# Regulation_Charging.net
KiCad netlist of a schematic drawn in Altium Designer
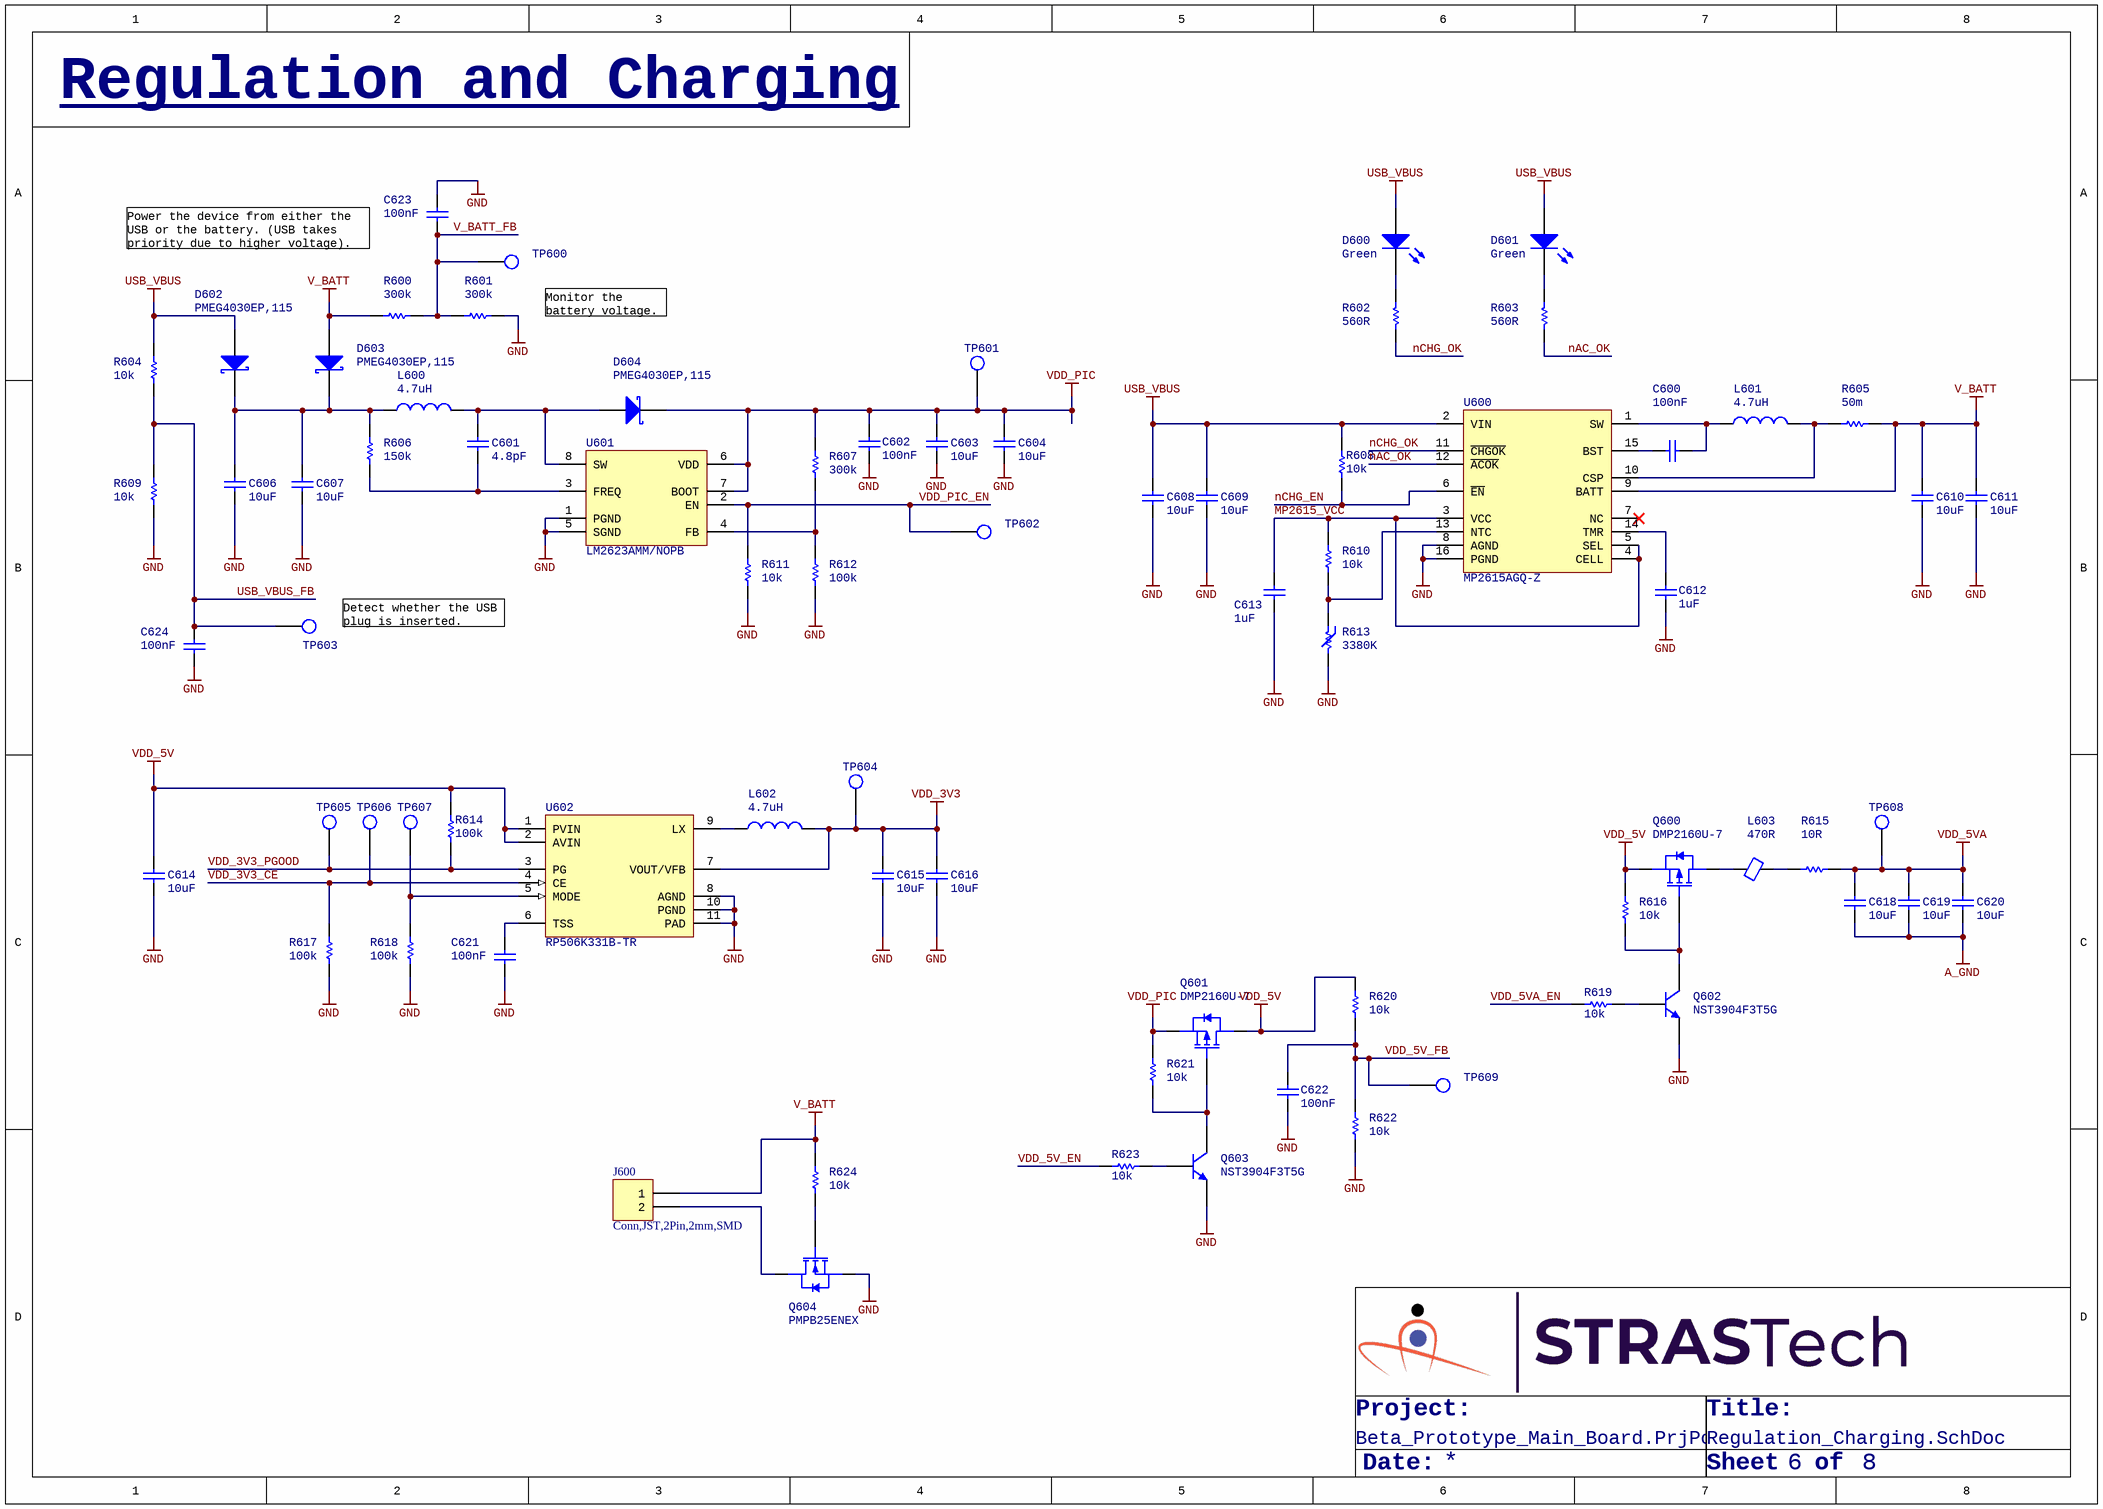
[diagram p0: Regulation_Charging.SchDoc]

(export (version "E")
  (design (tool "Eeschema 10.0.6"))
  (components
    (comp (ref "C600")
      (value "100nF")
      (footprint "Cap,SMD,0402")
      (description "0.1µF ±10% 25V Ceramic Capacitor X7R 0402 (1005 Metric)")
      (fields
        (field (name "VENDOR PART NUMBER") "490-14603-1-ND")
        (field (name "MANUFACTURER") "Murata Electronics")
        (field (name "CREATEDBY") "Judd Foster")
      )
      (libsource (lib "symbols") (part "CAP,Cer,100nF,25VDC,X7R,0402"))
    )
    (comp (ref "C601")
      (value "4.8pF")
      (footprint "Cap,SMD,0402")
      (description "4.8 pF ±0.25pF 50V Ceramic Capacitor C0G, NP0 0402 (1005 Metric)")
      (fields
        (field (name "VENDOR PART NUMBER") "490-17481-1-ND")
        (field (name "MANUFACTURER") "Murata Electronics")
        (field (name "CREATEDBY") "Judd Foster")
      )
      (libsource (lib "symbols") (part "CAP,Cer,4.8pF,50VDC,C0G/NP0,0402"))
    )
    (comp (ref "C602")
      (value "100nF")
      (footprint "Cap,SMD,0402")
      (description "0.1µF ±10% 25V Ceramic Capacitor X7R 0402 (1005 Metric)")
      (fields
        (field (name "VENDOR PART NUMBER") "490-14603-1-ND")
        (field (name "MANUFACTURER") "Murata Electronics")
        (field (name "CREATEDBY") "Judd Foster")
      )
      (libsource (lib "symbols") (part "CAP,Cer,100nF,25VDC,X7R,0402"))
    )
    (comp (ref "C603")
      (value "10uF")
      (footprint "Cap,SMD,0402")
      (description "10 µF ±20% 10V Ceramic Capacitor X5R 0402 (1005 Metric)")
      (fields
        (field (name "VENDOR PART NUMBER") "1276-1450-1-ND")
        (field (name "MANUFACTURER") "Samsung Electro-Mechanics")
        (field (name "CREATEDBY") "Judd Foster")
      )
      (libsource (lib "symbols") (part "CAP,Cer,10uF,10VDC,X5R,0402"))
    )
    (comp (ref "C604")
      (value "10uF")
      (footprint "Cap,SMD,0402")
      (description "10 µF ±20% 10V Ceramic Capacitor X5R 0402 (1005 Metric)")
      (fields
        (field (name "VENDOR PART NUMBER") "1276-1450-1-ND")
        (field (name "MANUFACTURER") "Samsung Electro-Mechanics")
        (field (name "CREATEDBY") "Judd Foster")
      )
      (libsource (lib "symbols") (part "CAP,Cer,10uF,10VDC,X5R,0402"))
    )
    (comp (ref "C606")
      (value "10uF")
      (footprint "Cap,SMD,0402")
      (description "10 µF ±20% 10V Ceramic Capacitor X5R 0402 (1005 Metric)")
      (fields
        (field (name "VENDOR PART NUMBER") "1276-1450-1-ND")
        (field (name "MANUFACTURER") "Samsung Electro-Mechanics")
        (field (name "CREATEDBY") "Judd Foster")
      )
      (libsource (lib "symbols") (part "CAP,Cer,10uF,10VDC,X5R,0402"))
    )
    (comp (ref "C607")
      (value "10uF")
      (footprint "Cap,SMD,0402")
      (description "10 µF ±20% 10V Ceramic Capacitor X5R 0402 (1005 Metric)")
      (fields
        (field (name "VENDOR PART NUMBER") "1276-1450-1-ND")
        (field (name "MANUFACTURER") "Samsung Electro-Mechanics")
        (field (name "CREATEDBY") "Judd Foster")
      )
      (libsource (lib "symbols") (part "CAP,Cer,10uF,10VDC,X5R,0402"))
    )
    (comp (ref "C608")
      (value "10uF")
      (footprint "Cap,SMD,0402")
      (description "10 µF ±20% 10V Ceramic Capacitor X5R 0402 (1005 Metric)")
      (fields
        (field (name "VENDOR PART NUMBER") "1276-1450-1-ND")
        (field (name "MANUFACTURER") "Samsung Electro-Mechanics")
        (field (name "CREATEDBY") "Judd Foster")
      )
      (libsource (lib "symbols") (part "CAP,Cer,10uF,10VDC,X5R,0402"))
    )
    (comp (ref "C609")
      (value "10uF")
      (footprint "Cap,SMD,0402")
      (description "10 µF ±20% 10V Ceramic Capacitor X5R 0402 (1005 Metric)")
      (fields
        (field (name "VENDOR PART NUMBER") "1276-1450-1-ND")
        (field (name "MANUFACTURER") "Samsung Electro-Mechanics")
        (field (name "CREATEDBY") "Judd Foster")
      )
      (libsource (lib "symbols") (part "CAP,Cer,10uF,10VDC,X5R,0402"))
    )
    (comp (ref "C610")
      (value "10uF")
      (footprint "Cap,SMD,0402")
      (description "10 µF ±20% 10V Ceramic Capacitor X5R 0402 (1005 Metric)")
      (fields
        (field (name "VENDOR PART NUMBER") "1276-1450-1-ND")
        (field (name "MANUFACTURER") "Samsung Electro-Mechanics")
        (field (name "CREATEDBY") "Judd Foster")
      )
      (libsource (lib "symbols") (part "CAP,Cer,10uF,10VDC,X5R,0402"))
    )
    (comp (ref "C611")
      (value "10uF")
      (footprint "Cap,SMD,0402")
      (description "10 µF ±20% 10V Ceramic Capacitor X5R 0402 (1005 Metric)")
      (fields
        (field (name "VENDOR PART NUMBER") "1276-1450-1-ND")
        (field (name "MANUFACTURER") "Samsung Electro-Mechanics")
        (field (name "CREATEDBY") "Judd Foster")
      )
      (libsource (lib "symbols") (part "CAP,Cer,10uF,10VDC,X5R,0402"))
    )
    (comp (ref "C612")
      (value "1uF")
      (footprint "Cap,SMD,0402")
      (description "1 µF ±10% 35V Ceramic Capacitor X5R 0402 (1005 Metric)")
      (fields
        (field (name "VENDOR PART NUMBER") "445-9073-1-ND")
        (field (name "MANUFACTURER") "TDK Corporation")
        (field (name "CREATEDBY") "Judd Foster")
      )
      (libsource (lib "symbols") (part "CAP,Cer,1uF,35VDC,X5R,0402"))
    )
    (comp (ref "C613")
      (value "1uF")
      (footprint "Cap,SMD,0402")
      (description "1 µF ±10% 35V Ceramic Capacitor X5R 0402 (1005 Metric)")
      (fields
        (field (name "VENDOR PART NUMBER") "445-9073-1-ND")
        (field (name "MANUFACTURER") "TDK Corporation")
        (field (name "CREATEDBY") "Judd Foster")
      )
      (libsource (lib "symbols") (part "CAP,Cer,1uF,35VDC,X5R,0402"))
    )
    (comp (ref "C614")
      (value "10uF")
      (footprint "Cap,SMD,0402")
      (description "10 µF ±20% 10V Ceramic Capacitor X5R 0402 (1005 Metric)")
      (fields
        (field (name "VENDOR PART NUMBER") "1276-1450-1-ND")
        (field (name "MANUFACTURER") "Samsung Electro-Mechanics")
        (field (name "CREATEDBY") "Judd Foster")
      )
      (libsource (lib "symbols") (part "CAP,Cer,10uF,10VDC,X5R,0402"))
    )
    (comp (ref "C615")
      (value "10uF")
      (footprint "Cap,SMD,0402")
      (description "10 µF ±20% 10V Ceramic Capacitor X5R 0402 (1005 Metric)")
      (fields
        (field (name "VENDOR PART NUMBER") "1276-1450-1-ND")
        (field (name "MANUFACTURER") "Samsung Electro-Mechanics")
        (field (name "CREATEDBY") "Judd Foster")
      )
      (libsource (lib "symbols") (part "CAP,Cer,10uF,10VDC,X5R,0402"))
    )
    (comp (ref "C616")
      (value "10uF")
      (footprint "Cap,SMD,0402")
      (description "10 µF ±20% 10V Ceramic Capacitor X5R 0402 (1005 Metric)")
      (fields
        (field (name "VENDOR PART NUMBER") "1276-1450-1-ND")
        (field (name "MANUFACTURER") "Samsung Electro-Mechanics")
        (field (name "CREATEDBY") "Judd Foster")
      )
      (libsource (lib "symbols") (part "CAP,Cer,10uF,10VDC,X5R,0402"))
    )
    (comp (ref "C618")
      (value "10uF")
      (footprint "Cap,SMD,0402")
      (description "10 µF ±20% 10V Ceramic Capacitor X5R 0402 (1005 Metric)")
      (fields
        (field (name "VENDOR PART NUMBER") "1276-1450-1-ND")
        (field (name "MANUFACTURER") "Samsung Electro-Mechanics")
        (field (name "CREATEDBY") "Judd Foster")
      )
      (libsource (lib "symbols") (part "CAP,Cer,10uF,10VDC,X5R,0402"))
    )
    (comp (ref "C619")
      (value "10uF")
      (footprint "Cap,SMD,0402")
      (description "10 µF ±20% 10V Ceramic Capacitor X5R 0402 (1005 Metric)")
      (fields
        (field (name "VENDOR PART NUMBER") "1276-1450-1-ND")
        (field (name "MANUFACTURER") "Samsung Electro-Mechanics")
        (field (name "CREATEDBY") "Judd Foster")
      )
      (libsource (lib "symbols") (part "CAP,Cer,10uF,10VDC,X5R,0402"))
    )
    (comp (ref "C620")
      (value "10uF")
      (footprint "Cap,SMD,0402")
      (description "10 µF ±20% 10V Ceramic Capacitor X5R 0402 (1005 Metric)")
      (fields
        (field (name "VENDOR PART NUMBER") "1276-1450-1-ND")
        (field (name "MANUFACTURER") "Samsung Electro-Mechanics")
        (field (name "CREATEDBY") "Judd Foster")
      )
      (libsource (lib "symbols") (part "CAP,Cer,10uF,10VDC,X5R,0402"))
    )
    (comp (ref "C621")
      (value "100nF")
      (footprint "Cap,SMD,0402")
      (description "0.1µF ±10% 25V Ceramic Capacitor X7R 0402 (1005 Metric)")
      (fields
        (field (name "VENDOR PART NUMBER") "490-14603-1-ND")
        (field (name "MANUFACTURER") "Murata Electronics")
        (field (name "CREATEDBY") "Judd Foster")
      )
      (libsource (lib "symbols") (part "CAP,Cer,100nF,25VDC,X7R,0402"))
    )
    (comp (ref "C622")
      (value "100nF")
      (footprint "Cap,SMD,0402")
      (description "0.1µF ±10% 25V Ceramic Capacitor X7R 0402 (1005 Metric)")
      (fields
        (field (name "VENDOR PART NUMBER") "490-14603-1-ND")
        (field (name "MANUFACTURER") "Murata Electronics")
        (field (name "CREATEDBY") "Judd Foster")
      )
      (libsource (lib "symbols") (part "CAP,Cer,100nF,25VDC,X7R,0402"))
    )
    (comp (ref "C623")
      (value "100nF")
      (footprint "Cap,SMD,0402")
      (description "0.1µF ±10% 25V Ceramic Capacitor X7R 0402 (1005 Metric)")
      (fields
        (field (name "VENDOR PART NUMBER") "490-14603-1-ND")
        (field (name "MANUFACTURER") "Murata Electronics")
        (field (name "CREATEDBY") "Judd Foster")
      )
      (libsource (lib "symbols") (part "CAP,Cer,100nF,25VDC,X7R,0402"))
    )
    (comp (ref "C624")
      (value "100nF")
      (footprint "Cap,SMD,0402")
      (description "0.1µF ±10% 25V Ceramic Capacitor X7R 0402 (1005 Metric)")
      (fields
        (field (name "VENDOR PART NUMBER") "490-14603-1-ND")
        (field (name "MANUFACTURER") "Murata Electronics")
        (field (name "CREATEDBY") "Judd Foster")
      )
      (libsource (lib "symbols") (part "CAP,Cer,100nF,25VDC,X7R,0402"))
    )
    (comp (ref "D600")
      (value "Green")
      (footprint "LED,0603")
      (description "Green 530nm LED Indication - Discrete 3V 0603 (1608 Metric)")
      (fields
        (field (name "MANUFACTURER") "Stanley Electric Co")
        (field (name "MANUFACTURER PART NUMBER") "THG1111C-0005-TR")
        (field (name "CREATEDBY") "Judd Foster")
      )
      (libsource (lib "symbols") (part "LED,Green,SMD,0603"))
    )
    (comp (ref "D601")
      (value "Green")
      (footprint "LED,0603")
      (description "Green 530nm LED Indication - Discrete 3V 0603 (1608 Metric)")
      (fields
        (field (name "MANUFACTURER") "Stanley Electric Co")
        (field (name "MANUFACTURER PART NUMBER") "THG1111C-0005-TR")
        (field (name "CREATEDBY") "Judd Foster")
      )
      (libsource (lib "symbols") (part "LED,Green,SMD,0603"))
    )
    (comp (ref "D602")
      (value "PMEG4030EP,115")
      (footprint "SOD128")
      (description "Diode Schottky 40V 3A Surface Mount CFP5")
      (fields
        (field (name "MANUFACTURER") "Nexperia USA Inc.")
        (field (name "VENDOR PART NUMBER") "1727-5841-1-ND")
        (field (name "CREATEDBY") "Judd Foster")
      )
      (libsource (lib "symbols") (part "DIODE,Schottky,40V,3A,SMD"))
    )
    (comp (ref "D603")
      (value "PMEG4030EP,115")
      (footprint "SOD128")
      (description "Diode Schottky 40V 3A Surface Mount CFP5")
      (fields
        (field (name "MANUFACTURER") "Nexperia USA Inc.")
        (field (name "VENDOR PART NUMBER") "1727-5841-1-ND")
        (field (name "CREATEDBY") "Judd Foster")
      )
      (libsource (lib "symbols") (part "DIODE,Schottky,40V,3A,SMD"))
    )
    (comp (ref "D604")
      (value "PMEG4030EP,115")
      (footprint "SOD128")
      (description "Diode Schottky 40V 3A Surface Mount CFP5")
      (fields
        (field (name "MANUFACTURER") "Nexperia USA Inc.")
        (field (name "VENDOR PART NUMBER") "1727-5841-1-ND")
        (field (name "CREATEDBY") "Judd Foster")
      )
      (libsource (lib "symbols") (part "DIODE,Schottky,40V,3A,SMD"))
    )
    (comp (ref "J600")
      (value "Conn,JST,2Pin,2mm,SMD")
      (footprint "Conn,JST,2Pin,2mm,SMD")
      (description "Connector Header Surface Mount, Right Angle 2 position 0.079\" (2.00mm)")
      (fields
        (field (name "VENDOR PART NUMBER") "H125443CT-ND")
        (field (name "MANUFACTURER") "Hirose Electric Co Ltd")
        (field (name "CREATED BY") "Judd Foster")
      )
      (libsource (lib "symbols") (part "Conn,JST,2Pin,2mm,SMD"))
    )
    (comp (ref "L600")
      (value "4.7uH")
      (footprint "IND,WIREWOUND,4.9x4.9,SMD")
      (description "4.7µH Shielded Wirewound Inductor 2.6A 45.5mOhm Max Nonstandard")
      (fields
        (field (name "VENDOR PART NUMBER") "587-3605-1-ND")
        (field (name "MANUFACTURER") "Taiyo Yuden")
        (field (name "CREATEDBY") "Judd Foster")
      )
      (libsource (lib "symbols") (part "IND,4.7uH,2.6A,Wirewound,SMD"))
    )
    (comp (ref "L601")
      (value "4.7uH")
      (footprint "IND,WIREWOUND,4.9x4.9,SMD")
      (description "4.7µH Shielded Wirewound Inductor 2.6A 45.5mOhm Max Nonstandard")
      (fields
        (field (name "VENDOR PART NUMBER") "587-3605-1-ND")
        (field (name "MANUFACTURER") "Taiyo Yuden")
        (field (name "CREATEDBY") "Judd Foster")
      )
      (libsource (lib "symbols") (part "IND,4.7uH,2.6A,Wirewound,SMD"))
    )
    (comp (ref "L602")
      (value "4.7uH")
      (footprint "IND,WIREWOUND,4.9x4.9,SMD")
      (description "4.7µH Shielded Wirewound Inductor 2.6A 45.5mOhm Max Nonstandard")
      (fields
        (field (name "VENDOR PART NUMBER") "587-3605-1-ND")
        (field (name "MANUFACTURER") "Taiyo Yuden")
        (field (name "CREATEDBY") "Judd Foster")
      )
      (libsource (lib "symbols") (part "IND,4.7uH,2.6A,Wirewound,SMD"))
    )
    (comp (ref "L603")
      (value "470R")
      (footprint "IND,0402")
      (description "470 Ohms @ 100 MHz 1 Power Line Ferrite Bead 0402 (1005 Metric) 1A 200mOhm")
      (fields
        (field (name "VENDOR PART NUMBER") "490-10662-1-ND")
        (field (name "MANUFACTURER") "Murata Electronics")
        (field (name "CREATEDBY") "Judd Foster")
      )
      (libsource (lib "symbols") (part "Ferrite,470R@100MHz,0402"))
    )
    (comp (ref "Q600")
      (value "DMP2160U-7")
      (footprint "SOT23-3")
      (description "P-Channel 20 V 3.2A (Ta) 1.4W (Ta) Surface Mount SOT-23-3")
      (fields
        (field (name "MANUFACTURER") "Diodes Incorporated")
        (field (name "VENDOR PART NUMBER") "DMP2160UDICT-ND")
        (field (name "CREATEDBY") "Judd Foster")
      )
      (libsource (lib "symbols") (part "MOSFET,P Ch,20V,3.2A"))
    )
    (comp (ref "Q601")
      (value "DMP2160U-7")
      (footprint "SOT23-3")
      (description "P-Channel 20 V 3.2A (Ta) 1.4W (Ta) Surface Mount SOT-23-3")
      (fields
        (field (name "MANUFACTURER") "Diodes Incorporated")
        (field (name "VENDOR PART NUMBER") "DMP2160UDICT-ND")
        (field (name "CREATEDBY") "Judd Foster")
      )
      (libsource (lib "symbols") (part "MOSFET,P Ch,20V,3.2A"))
    )
    (comp (ref "Q602")
      (value "NST3904F3T5G")
      (footprint "SOT1123")
      (description "Bipolar (BJT) Transistor NPN 40 V 200 mA 200MHz 290 mW Surface Mount SOT-1123")
      (fields
        (field (name "MANUFACTURER") "ON Semiconductor")
        (field (name "VENDOR PART NUMBER") "NST3904F3T5GOSCT-ND")
        (field (name "CREATEDBY") "Judd Foster")
      )
      (libsource (lib "symbols") (part "Trans,NPN,40V,200mA,SOT1123"))
    )
    (comp (ref "Q603")
      (value "NST3904F3T5G")
      (footprint "SOT1123")
      (description "Bipolar (BJT) Transistor NPN 40 V 200 mA 200MHz 290 mW Surface Mount SOT-1123")
      (fields
        (field (name "MANUFACTURER") "ON Semiconductor")
        (field (name "VENDOR PART NUMBER") "NST3904F3T5GOSCT-ND")
        (field (name "CREATEDBY") "Judd Foster")
      )
      (libsource (lib "symbols") (part "Trans,NPN,40V,200mA,SOT1123"))
    )
    (comp (ref "Q604")
      (value "PMPB25ENEX")
      (footprint "IC,WDFN-6,P0.65")
      (description "N-Channel 30 V 10A (Ta) 2.1W (Ta) Surface Mount DFN2020MD-6")
      (fields
        (field (name "MANUFACTURER") "Nexperia USA Inc.")
        (field (name "VENDOR PART NUMBER") "1727-7662-1-ND")
        (field (name "CREATEDBY") "Ritesh Nandakumar")
      )
      (libsource (lib "symbols") (part "MOSFET,N Ch,30V,10A"))
    )
    (comp (ref "R600")
      (value "300k")
      (footprint "RES,0402")
      (description "300 kOhms ±1% 0.063W, 1/16W Chip Resistor 0402 (1005 Metric) Automotive AEC-Q200 Thick Film")
      (fields
        (field (name "MANUFACTURER") "Stackpole Electronics Inc")
        (field (name "MANUFACTURER PART NUMBER") "RMCF0402FT300K")
        (field (name "CREATEDBY") "Judd Foster")
      )
      (libsource (lib "symbols") (part "RES,300k,1%,0.063W,0402"))
    )
    (comp (ref "R601")
      (value "300k")
      (footprint "RES,0402")
      (description "300 kOhms ±1% 0.063W, 1/16W Chip Resistor 0402 (1005 Metric) Automotive AEC-Q200 Thick Film")
      (fields
        (field (name "MANUFACTURER") "Stackpole Electronics Inc")
        (field (name "MANUFACTURER PART NUMBER") "RMCF0402FT300K")
        (field (name "CREATEDBY") "Judd Foster")
      )
      (libsource (lib "symbols") (part "RES,300k,1%,0.063W,0402"))
    )
    (comp (ref "R602")
      (value "560R")
      (footprint "RES,0402")
      (fields
        (field (name "MANUFACTURER") "TE Connectivity Passive Product")
        (field (name "MANUFACTURER PART NUMBER") "CRGCQ0402F560R")
        (field (name "VENDOR PART NUMBER") "A129624CT-ND")
        (field (name "CREATEDBY") "Judd Foster")
      )
      (libsource (lib "symbols") (part "RES,560R,1%,0.063W,0402"))
    )
    (comp (ref "R603")
      (value "560R")
      (footprint "RES,0402")
      (fields
        (field (name "MANUFACTURER") "TE Connectivity Passive Product")
        (field (name "MANUFACTURER PART NUMBER") "CRGCQ0402F560R")
        (field (name "VENDOR PART NUMBER") "A129624CT-ND")
        (field (name "CREATEDBY") "Judd Foster")
      )
      (libsource (lib "symbols") (part "RES,560R,1%,0.063W,0402"))
    )
    (comp (ref "R604")
      (value "10k")
      (footprint "RES,0402")
      (description "10 kOhms ±5% 0.063W, 1/16W Chip Resistor 0402 (1005 Metric) Automotive AEC-Q200 Thick Film")
      (fields
        (field (name "VENDOR PART NUMBER") "RMCF0402JT10K0CT-ND")
        (field (name "MANUFACTURER") "Stackpole Electronics Inc")
        (field (name "CREATEDBY") "Judd Foster")
      )
      (libsource (lib "symbols") (part "RES,10k,5%,0.063W,0402"))
    )
    (comp (ref "R605")
      (value "50m")
      (footprint "RES,1206")
      (description "50 mOhms ±1% 0.5W, 1/2W Chip Resistor 1206 (3216 Metric) Current Sense Metal Film")
      (fields
        (field (name "MANUFACTURER") "Ohmite")
        (field (name "MANUFACTURER PART NUMBER") "KDV12FR050ET")
        (field (name "CREATEDBY") "Judd Foster")
      )
      (libsource (lib "symbols") (part "RES,50m,1%,0.5W,1206"))
    )
    (comp (ref "R606")
      (value "150k")
      (footprint "RES,0402")
      (description "150 kOhms ±1% 0.063W, 1/16W Chip Resistor 0402 (1005 Metric) Automotive AEC-Q200 Thick Film")
      (fields
        (field (name "MANUFACTURER") "Stackpole Electronics Inc")
        (field (name "MANUFACTURER PART NUMBER") "RMCF0402FT150K")
        (field (name "CREATEDBY") "Judd Foster")
      )
      (libsource (lib "symbols") (part "RES,150k,1%,0.1W,0402"))
    )
    (comp (ref "R607")
      (value "300k")
      (footprint "RES,0402")
      (description "300 kOhms ±1% 0.063W, 1/16W Chip Resistor 0402 (1005 Metric) Automotive AEC-Q200 Thick Film")
      (fields
        (field (name "MANUFACTURER") "Stackpole Electronics Inc")
        (field (name "MANUFACTURER PART NUMBER") "RMCF0402FT300K")
        (field (name "CREATEDBY") "Judd Foster")
      )
      (libsource (lib "symbols") (part "RES,300k,1%,0.063W,0402"))
    )
    (comp (ref "R608")
      (value "10k")
      (footprint "RES,0402")
      (description "10 kOhms ±5% 0.063W, 1/16W Chip Resistor 0402 (1005 Metric) Automotive AEC-Q200 Thick Film")
      (fields
        (field (name "VENDOR PART NUMBER") "RMCF0402JT10K0CT-ND")
        (field (name "MANUFACTURER") "Stackpole Electronics Inc")
        (field (name "CREATEDBY") "Judd Foster")
      )
      (libsource (lib "symbols") (part "RES,10k,5%,0.063W,0402"))
    )
    (comp (ref "R609")
      (value "10k")
      (footprint "RES,0402")
      (description "10 kOhms ±5% 0.063W, 1/16W Chip Resistor 0402 (1005 Metric) Automotive AEC-Q200 Thick Film")
      (fields
        (field (name "VENDOR PART NUMBER") "RMCF0402JT10K0CT-ND")
        (field (name "MANUFACTURER") "Stackpole Electronics Inc")
        (field (name "CREATEDBY") "Judd Foster")
      )
      (libsource (lib "symbols") (part "RES,10k,5%,0.063W,0402"))
    )
    (comp (ref "R610")
      (value "10k")
      (footprint "RES,0402")
      (description "10 kOhms ±5% 0.063W, 1/16W Chip Resistor 0402 (1005 Metric) Automotive AEC-Q200 Thick Film")
      (fields
        (field (name "VENDOR PART NUMBER") "RMCF0402JT10K0CT-ND")
        (field (name "MANUFACTURER") "Stackpole Electronics Inc")
        (field (name "CREATEDBY") "Judd Foster")
      )
      (libsource (lib "symbols") (part "RES,10k,5%,0.063W,0402"))
    )
    (comp (ref "R611")
      (value "10k")
      (footprint "RES,0402")
      (description "10 kOhms ±5% 0.063W, 1/16W Chip Resistor 0402 (1005 Metric) Automotive AEC-Q200 Thick Film")
      (fields
        (field (name "VENDOR PART NUMBER") "RMCF0402JT10K0CT-ND")
        (field (name "MANUFACTURER") "Stackpole Electronics Inc")
        (field (name "CREATEDBY") "Judd Foster")
      )
      (libsource (lib "symbols") (part "RES,10k,5%,0.063W,0402"))
    )
    (comp (ref "R612")
      (value "100k")
      (footprint "RES,0402")
      (description "100 kOhms ±5% 0.1W, 1/10W Chip Resistor 0402 (1005 Metric) Automotive AEC-Q200 Thick Film")
      (fields
        (field (name "MANUFACTURER") "Panasonic Electronic Components")
        (field (name "MANUFACTURER PART NUMBER") "ERJ-2GEJ104X")
        (field (name "CREATEDBY") "Judd Foster")
      )
      (libsource (lib "symbols") (part "RES,100k,5%,0.1W,0402"))
    )
    (comp (ref "R613")
      (value "3380K")
      (footprint "RES,0402")
      (description "NTC Thermistor 10k 0402 (1005 Metric)")
      (fields
        (field (name "MANUFACTURER") "Murata Electronics")
        (field (name "MANUFACTURER PART NUMBER") "NCU15XH103J6SRC")
        (field (name "CREATEDBY") "Judd Foster")
      )
      (libsource (lib "symbols") (part "RES,Thermistor,3380K,0402"))
    )
    (comp (ref "R614")
      (value "100k")
      (footprint "RES,0402")
      (description "100 kOhms ±5% 0.1W, 1/10W Chip Resistor 0402 (1005 Metric) Automotive AEC-Q200 Thick Film")
      (fields
        (field (name "MANUFACTURER") "Panasonic Electronic Components")
        (field (name "MANUFACTURER PART NUMBER") "ERJ-2GEJ104X")
        (field (name "CREATEDBY") "Judd Foster")
      )
      (libsource (lib "symbols") (part "RES,100k,5%,0.1W,0402"))
    )
    (comp (ref "R615")
      (value "10R")
      (footprint "RES,0402")
      (description "10 Ohms ±1% 0.063W, 1/16W Chip Resistor 0402 (1005 Metric) Automotive AEC-Q200 Thick Film")
      (fields
        (field (name "MANUFACTURER") "Panasonic Electronic Components")
        (field (name "MANUFACTURER PART NUMBER") "ERJ-2RKF10R0X")
        (field (name "CREATEDBY") "Judd Foster")
      )
      (libsource (lib "symbols") (part "RES,10R,1%,0.063W,0402"))
    )
    (comp (ref "R616")
      (value "10k")
      (footprint "RES,0402")
      (description "10 kOhms ±5% 0.063W, 1/16W Chip Resistor 0402 (1005 Metric) Automotive AEC-Q200 Thick Film")
      (fields
        (field (name "VENDOR PART NUMBER") "RMCF0402JT10K0CT-ND")
        (field (name "MANUFACTURER") "Stackpole Electronics Inc")
        (field (name "CREATEDBY") "Judd Foster")
      )
      (libsource (lib "symbols") (part "RES,10k,5%,0.063W,0402"))
    )
    (comp (ref "R617")
      (value "100k")
      (footprint "RES,0402")
      (description "100 kOhms ±5% 0.1W, 1/10W Chip Resistor 0402 (1005 Metric) Automotive AEC-Q200 Thick Film")
      (fields
        (field (name "MANUFACTURER") "Panasonic Electronic Components")
        (field (name "MANUFACTURER PART NUMBER") "ERJ-2GEJ104X")
        (field (name "CREATEDBY") "Judd Foster")
      )
      (libsource (lib "symbols") (part "RES,100k,5%,0.1W,0402"))
    )
    (comp (ref "R618")
      (value "100k")
      (footprint "RES,0402")
      (description "100 kOhms ±5% 0.1W, 1/10W Chip Resistor 0402 (1005 Metric) Automotive AEC-Q200 Thick Film")
      (fields
        (field (name "MANUFACTURER") "Panasonic Electronic Components")
        (field (name "MANUFACTURER PART NUMBER") "ERJ-2GEJ104X")
        (field (name "CREATEDBY") "Judd Foster")
      )
      (libsource (lib "symbols") (part "RES,100k,5%,0.1W,0402"))
    )
    (comp (ref "R619")
      (value "10k")
      (footprint "RES,0402")
      (description "10 kOhms ±5% 0.063W, 1/16W Chip Resistor 0402 (1005 Metric) Automotive AEC-Q200 Thick Film")
      (fields
        (field (name "VENDOR PART NUMBER") "RMCF0402JT10K0CT-ND")
        (field (name "MANUFACTURER") "Stackpole Electronics Inc")
        (field (name "CREATEDBY") "Judd Foster")
      )
      (libsource (lib "symbols") (part "RES,10k,5%,0.063W,0402"))
    )
    (comp (ref "R620")
      (value "10k")
      (footprint "RES,0402")
      (description "10 kOhms ±5% 0.063W, 1/16W Chip Resistor 0402 (1005 Metric) Automotive AEC-Q200 Thick Film")
      (fields
        (field (name "VENDOR PART NUMBER") "RMCF0402JT10K0CT-ND")
        (field (name "MANUFACTURER") "Stackpole Electronics Inc")
        (field (name "CREATEDBY") "Judd Foster")
      )
      (libsource (lib "symbols") (part "RES,10k,5%,0.063W,0402"))
    )
    (comp (ref "R621")
      (value "10k")
      (footprint "RES,0402")
      (description "10 kOhms ±5% 0.063W, 1/16W Chip Resistor 0402 (1005 Metric) Automotive AEC-Q200 Thick Film")
      (fields
        (field (name "VENDOR PART NUMBER") "RMCF0402JT10K0CT-ND")
        (field (name "MANUFACTURER") "Stackpole Electronics Inc")
        (field (name "CREATEDBY") "Judd Foster")
      )
      (libsource (lib "symbols") (part "RES,10k,5%,0.063W,0402"))
    )
    (comp (ref "R622")
      (value "10k")
      (footprint "RES,0402")
      (description "10 kOhms ±5% 0.063W, 1/16W Chip Resistor 0402 (1005 Metric) Automotive AEC-Q200 Thick Film")
      (fields
        (field (name "VENDOR PART NUMBER") "RMCF0402JT10K0CT-ND")
        (field (name "MANUFACTURER") "Stackpole Electronics Inc")
        (field (name "CREATEDBY") "Judd Foster")
      )
      (libsource (lib "symbols") (part "RES,10k,5%,0.063W,0402"))
    )
    (comp (ref "R623")
      (value "10k")
      (footprint "RES,0402")
      (description "10 kOhms ±5% 0.063W, 1/16W Chip Resistor 0402 (1005 Metric) Automotive AEC-Q200 Thick Film")
      (fields
        (field (name "VENDOR PART NUMBER") "RMCF0402JT10K0CT-ND")
        (field (name "MANUFACTURER") "Stackpole Electronics Inc")
        (field (name "CREATEDBY") "Judd Foster")
      )
      (libsource (lib "symbols") (part "RES,10k,5%,0.063W,0402"))
    )
    (comp (ref "R624")
      (value "10k")
      (footprint "RES,0402")
      (description "10 kOhms ±5% 0.063W, 1/16W Chip Resistor 0402 (1005 Metric) Automotive AEC-Q200 Thick Film")
      (fields
        (field (name "VENDOR PART NUMBER") "RMCF0402JT10K0CT-ND")
        (field (name "MANUFACTURER") "Stackpole Electronics Inc")
        (field (name "CREATEDBY") "Judd Foster")
      )
      (libsource (lib "symbols") (part "RES,10k,5%,0.063W,0402"))
    )
    (comp (ref "TP600")
      (value "TESTPOINT")
      (footprint "testpoint,smd,round,1mm")
      (description "PCB Testpoint")
      (fields (field (name "CREATEDBY") "Judd Foster"))
      (libsource (lib "symbols") (part "TESTPOINT"))
    )
    (comp (ref "TP601")
      (value "TESTPOINT")
      (footprint "testpoint,smd,round,1mm")
      (description "PCB Testpoint")
      (fields (field (name "CREATEDBY") "Judd Foster"))
      (libsource (lib "symbols") (part "TESTPOINT"))
    )
    (comp (ref "TP602")
      (value "TESTPOINT")
      (footprint "testpoint,smd,round,1mm")
      (description "PCB Testpoint")
      (fields (field (name "CREATEDBY") "Judd Foster"))
      (libsource (lib "symbols") (part "TESTPOINT"))
    )
    (comp (ref "TP603")
      (value "TESTPOINT")
      (footprint "testpoint,smd,round,1mm")
      (description "PCB Testpoint")
      (fields (field (name "CREATEDBY") "Judd Foster"))
      (libsource (lib "symbols") (part "TESTPOINT"))
    )
    (comp (ref "TP604")
      (value "TESTPOINT")
      (footprint "testpoint,smd,round,1mm")
      (description "PCB Testpoint")
      (fields (field (name "CREATEDBY") "Judd Foster"))
      (libsource (lib "symbols") (part "TESTPOINT"))
    )
    (comp (ref "TP605")
      (value "TESTPOINT")
      (footprint "testpoint,smd,round,1mm")
      (description "PCB Testpoint")
      (fields (field (name "CREATEDBY") "Judd Foster"))
      (libsource (lib "symbols") (part "TESTPOINT"))
    )
    (comp (ref "TP606")
      (value "TESTPOINT")
      (footprint "testpoint,smd,round,1mm")
      (description "PCB Testpoint")
      (fields (field (name "CREATEDBY") "Judd Foster"))
      (libsource (lib "symbols") (part "TESTPOINT"))
    )
    (comp (ref "TP607")
      (value "TESTPOINT")
      (footprint "testpoint,smd,round,1mm")
      (description "PCB Testpoint")
      (fields (field (name "CREATEDBY") "Judd Foster"))
      (libsource (lib "symbols") (part "TESTPOINT"))
    )
    (comp (ref "TP608")
      (value "TESTPOINT")
      (footprint "testpoint,smd,round,1mm")
      (description "PCB Testpoint")
      (fields (field (name "CREATEDBY") "Judd Foster"))
      (libsource (lib "symbols") (part "TESTPOINT"))
    )
    (comp (ref "TP609")
      (value "TESTPOINT")
      (footprint "testpoint,smd,round,1mm")
      (description "PCB Testpoint")
      (fields (field (name "CREATEDBY") "Judd Foster"))
      (libsource (lib "symbols") (part "TESTPOINT"))
    )
    (comp (ref "U600")
      (value "MP2615AGQ-Z")
      (footprint "IC,QFN-16,3x3,P5x3")
      (description "Charger IC Lithium Ion/Polymer 16-QFN (3x3)")
      (fields
        (field (name "MANUFACTURER") "Monolithic Power Systems Inc.")
        (field (name "VENDOR PART NUMBER") "1589-MP2615AGQ-ZCT-ND")
        (field (name "CREATEDBY") "Judd Foster")
      )
      (libsource (lib "symbols") (part "MP2615AGQ-Z"))
    )
    (comp (ref "U601")
      (value "LM2623AMM/NOPB")
      (footprint "IC,TSSOP-8,W3.0")
      (fields
        (field (name "VENDOR PART NUMBER") "LM2623AMM/NOPBCT-ND")
        (field (name "MANUFACTURER") "Texas Instruments")
        (field (name "CREATEDBY") "Judd Foster")
      )
      (libsource (lib "symbols") (part "LM2623AMM/NOPB"))
    )
    (comp (ref "U602")
      (value "RP506K331B-TR")
      (footprint "IC,DFN-10_3x3,P0.5mm")
      (description "Buck Switching Regulator IC Positive Fixed 3.3V 1 Output 2A 10-UFDFN Exposed Pad")
      (fields
        (field (name "MANUFACTURER") "Nisshinbo Micro Devices Inc.")
        (field (name "VENDOR PART NUMBER") "2129-RP506K331B-CT-ND")
        (field (name "CREATEDBY") "Judd Foster")
      )
      (libsource (lib "symbols") (part "RP506K331B-TR"))
    )
  )
  (nets
    (net (code "1") (name "/MP2615_VCC") (class "Default")
      (node (ref "C613") (pin "2") (pinfunction "2_2") (pintype "passive"))
      (node (ref "R610") (pin "1") (pinfunction "1_1") (pintype "passive"))
      (node (ref "U600") (pin "3") (pinfunction "VCC_3") (pintype "passive"))
      (node (ref "U600") (pin "4") (pinfunction "CELL_4") (pintype "passive"))
      (node (ref "U600") (pin "5") (pinfunction "SEL_5") (pintype "passive"))
    )
    (net (code "2") (name "/USB_VBUS_FB") (class "Default")
      (node (ref "C624") (pin "2") (pinfunction "2_2") (pintype "passive"))
      (node (ref "R604") (pin "1") (pinfunction "1_1") (pintype "passive"))
      (node (ref "R609") (pin "2") (pinfunction "2_2") (pintype "passive"))
      (node (ref "TP603") (pin "1") (pinfunction "TP_1") (pintype "passive"))
    )
    (net (code "3") (name "/VDD_3V3_CE") (class "Default")
      (node (ref "R617") (pin "2") (pinfunction "2_2") (pintype "passive"))
      (node (ref "TP606") (pin "1") (pinfunction "TP_1") (pintype "passive"))
      (node (ref "U602") (pin "4") (pinfunction "CE_4") (pintype "input"))
    )
    (net (code "4") (name "/VDD_3V3_PGOOD") (class "Default")
      (node (ref "R614") (pin "1") (pinfunction "1_1") (pintype "passive"))
      (node (ref "TP605") (pin "1") (pinfunction "TP_1") (pintype "passive"))
      (node (ref "U602") (pin "3") (pinfunction "PG_3") (pintype "open_collector"))
    )
    (net (code "5") (name "/VDD_5VA_EN") (class "Default")
      (node (ref "R619") (pin "2") (pinfunction "2_2") (pintype "passive"))
    )
    (net (code "6") (name "/VDD_5V_EN") (class "Default")
      (node (ref "R623") (pin "2") (pinfunction "2_2") (pintype "passive"))
    )
    (net (code "7") (name "/VDD_5V_FB") (class "Default")
      (node (ref "C622") (pin "1") (pinfunction "1_1") (pintype "passive"))
      (node (ref "R620") (pin "1") (pinfunction "1_1") (pintype "passive"))
      (node (ref "R622") (pin "2") (pinfunction "2_2") (pintype "passive"))
      (node (ref "TP609") (pin "1") (pinfunction "TP_1") (pintype "passive"))
    )
    (net (code "8") (name "/VDD_PIC_EN") (class "Default")
      (node (ref "R611") (pin "2") (pinfunction "2_2") (pintype "passive"))
      (node (ref "TP602") (pin "1") (pinfunction "TP_1") (pintype "passive"))
      (node (ref "U601") (pin "2") (pinfunction "EN_2") (pintype "passive"))
    )
    (net (code "9") (name "/V_BATT_FB") (class "Default")
      (node (ref "C623") (pin "1") (pinfunction "1_1") (pintype "passive"))
      (node (ref "R600") (pin "1") (pinfunction "1_1") (pintype "passive"))
      (node (ref "R601") (pin "2") (pinfunction "2_2") (pintype "passive"))
      (node (ref "TP600") (pin "1") (pinfunction "TP_1") (pintype "passive"))
    )
    (net (code "10") (name "/nAC_OK") (class "Default")
      (node (ref "R603") (pin "2") (pinfunction "2_2") (pintype "passive"))
      (node (ref "U600") (pin "12") (pinfunction "~{ACOK}_12") (pintype "passive"))
    )
    (net (code "11") (name "/nCHG_EN") (class "Default")
      (node (ref "R608") (pin "2") (pinfunction "2_2") (pintype "passive"))
      (node (ref "U600") (pin "6") (pinfunction "~{EN}_6") (pintype "passive"))
    )
    (net (code "12") (name "/nCHG_OK") (class "Default")
      (node (ref "R602") (pin "2") (pinfunction "2_2") (pintype "passive"))
      (node (ref "U600") (pin "11") (pinfunction "~{CHGOK}_11") (pintype "passive"))
    )
    (net (code "13") (name "A_GND") (class "Default")
      (node (ref "C618") (pin "1") (pinfunction "1_1") (pintype "passive"))
      (node (ref "C619") (pin "1") (pinfunction "1_1") (pintype "passive"))
      (node (ref "C620") (pin "1") (pinfunction "1_1") (pintype "passive"))
    )
    (net (code "14") (name "GND") (class "Default")
      (node (ref "C602") (pin "2") (pinfunction "2_2") (pintype "passive"))
      (node (ref "C603") (pin "1") (pinfunction "1_1") (pintype "passive"))
      (node (ref "C604") (pin "1") (pinfunction "1_1") (pintype "passive"))
      (node (ref "C606") (pin "1") (pinfunction "1_1") (pintype "passive"))
      (node (ref "C607") (pin "1") (pinfunction "1_1") (pintype "passive"))
      (node (ref "C608") (pin "1") (pinfunction "1_1") (pintype "passive"))
      (node (ref "C609") (pin "1") (pinfunction "1_1") (pintype "passive"))
      (node (ref "C610") (pin "1") (pinfunction "1_1") (pintype "passive"))
      (node (ref "C611") (pin "1") (pinfunction "1_1") (pintype "passive"))
      (node (ref "C612") (pin "2") (pinfunction "2_2") (pintype "passive"))
      (node (ref "C613") (pin "1") (pinfunction "1_1") (pintype "passive"))
      (node (ref "C614") (pin "1") (pinfunction "1_1") (pintype "passive"))
      (node (ref "C615") (pin "1") (pinfunction "1_1") (pintype "passive"))
      (node (ref "C616") (pin "1") (pinfunction "1_1") (pintype "passive"))
      (node (ref "C621") (pin "1") (pinfunction "1_1") (pintype "passive"))
      (node (ref "C622") (pin "2") (pinfunction "2_2") (pintype "passive"))
      (node (ref "C623") (pin "2") (pinfunction "2_2") (pintype "passive"))
      (node (ref "C624") (pin "1") (pinfunction "1_1") (pintype "passive"))
      (node (ref "Q602") (pin "2") (pinfunction "E_2") (pintype "passive"))
      (node (ref "Q603") (pin "2") (pinfunction "E_2") (pintype "passive"))
      (node (ref "Q604") (pin "3") (pinfunction "S_3") (pintype "passive"))
      (node (ref "R601") (pin "1") (pinfunction "1_1") (pintype "passive"))
      (node (ref "R609") (pin "1") (pinfunction "1_1") (pintype "passive"))
      (node (ref "R611") (pin "1") (pinfunction "1_1") (pintype "passive"))
      (node (ref "R612") (pin "1") (pinfunction "1_1") (pintype "passive"))
      (node (ref "R613") (pin "2") (pinfunction "2_2") (pintype "passive"))
      (node (ref "R617") (pin "1") (pinfunction "1_1") (pintype "passive"))
      (node (ref "R618") (pin "2") (pinfunction "2_2") (pintype "passive"))
      (node (ref "R622") (pin "1") (pinfunction "1_1") (pintype "passive"))
      (node (ref "U600") (pin "16") (pinfunction "PGND_16") (pintype "passive"))
      (node (ref "U600") (pin "8") (pinfunction "AGND_8") (pintype "passive"))
      (node (ref "U601") (pin "1") (pinfunction "PGND_1") (pintype "passive"))
      (node (ref "U601") (pin "5") (pinfunction "SGND_5") (pintype "passive"))
      (node (ref "U602") (pin "10") (pinfunction "PGND_10") (pintype "power_in"))
      (node (ref "U602") (pin "11") (pinfunction "PAD_11") (pintype "power_in"))
      (node (ref "U602") (pin "8") (pinfunction "AGND_8") (pintype "power_in"))
    )
    (net (code "15") (name "Net-(D600-K)") (class "Default")
      (node (ref "D600") (pin "2") (pinfunction "K_2") (pintype "passive"))
      (node (ref "R602") (pin "1") (pinfunction "1_1") (pintype "passive"))
    )
    (net (code "16") (name "Net-(D601-K)") (class "Default")
      (node (ref "D601") (pin "2") (pinfunction "K_2") (pintype "passive"))
      (node (ref "R603") (pin "1") (pinfunction "1_1") (pintype "passive"))
    )
    (net (code "17") (name "Net-(D602-K)") (class "Default")
      (node (ref "C606") (pin "2") (pinfunction "2_2") (pintype "passive"))
      (node (ref "C607") (pin "2") (pinfunction "2_2") (pintype "passive"))
      (node (ref "D602") (pin "1") (pinfunction "K_1") (pintype "passive"))
      (node (ref "D603") (pin "1") (pinfunction "K_1") (pintype "passive"))
      (node (ref "L600") (pin "1") (pinfunction "1_1") (pintype "passive"))
      (node (ref "R606") (pin "2") (pinfunction "2_2") (pintype "passive"))
    )
    (net (code "18") (name "Net-(D604-A)") (class "Default")
      (node (ref "C601") (pin "2") (pinfunction "2_2") (pintype "passive"))
      (node (ref "D604") (pin "2") (pinfunction "A_2") (pintype "passive"))
      (node (ref "L600") (pin "2") (pinfunction "2_2") (pintype "passive"))
      (node (ref "U601") (pin "8") (pinfunction "SW_8") (pintype "passive"))
    )
    (net (code "19") (name "Net-(L603-Pad2)") (class "Default")
      (node (ref "L603") (pin "2") (pinfunction "2_2") (pintype "passive"))
      (node (ref "R615") (pin "1") (pinfunction "1_1") (pintype "passive"))
    )
    (net (code "20") (name "Net-(Q600-D)") (class "Default")
      (node (ref "L603") (pin "1") (pinfunction "1_1") (pintype "passive"))
      (node (ref "Q600") (pin "3") (pinfunction "D_3") (pintype "passive"))
    )
    (net (code "21") (name "Net-(Q600-G)") (class "Default")
      (node (ref "Q600") (pin "1") (pinfunction "G_1") (pintype "passive"))
      (node (ref "Q602") (pin "3") (pinfunction "C_3") (pintype "passive"))
      (node (ref "R616") (pin "1") (pinfunction "1_1") (pintype "passive"))
    )
    (net (code "22") (name "Net-(Q601-G)") (class "Default")
      (node (ref "Q601") (pin "1") (pinfunction "G_1") (pintype "passive"))
      (node (ref "Q603") (pin "3") (pinfunction "C_3") (pintype "passive"))
      (node (ref "R621") (pin "1") (pinfunction "1_1") (pintype "passive"))
    )
    (net (code "23") (name "Net-(Q602-B)") (class "Default")
      (node (ref "Q602") (pin "1") (pinfunction "B_1") (pintype "passive"))
      (node (ref "R619") (pin "1") (pinfunction "1_1") (pintype "passive"))
    )
    (net (code "24") (name "Net-(Q603-B)") (class "Default")
      (node (ref "Q603") (pin "1") (pinfunction "B_1") (pintype "passive"))
      (node (ref "R623") (pin "1") (pinfunction "1_1") (pintype "passive"))
    )
    (net (code "25") (name "Net-(Q604-D)") (class "Default")
      (node (ref "J600") (pin "2") (pinfunction "2_2") (pintype "passive"))
      (node (ref "Q604") (pin "1") (pinfunction "D_1") (pintype "passive"))
    )
    (net (code "26") (name "Net-(Q604-G)") (class "Default")
      (node (ref "Q604") (pin "2") (pinfunction "G_2") (pintype "passive"))
      (node (ref "R624") (pin "1") (pinfunction "1_1") (pintype "passive"))
    )
    (net (code "27") (name "Net-(TP607-TP)") (class "Default")
      (node (ref "R618") (pin "1") (pinfunction "1_1") (pintype "passive"))
      (node (ref "TP607") (pin "1") (pinfunction "TP_1") (pintype "passive"))
      (node (ref "U602") (pin "5") (pinfunction "MODE_5") (pintype "input"))
    )
    (net (code "28") (name "Net-(U600-BST)") (class "Default")
      (node (ref "C600") (pin "2") (pinfunction "2_2") (pintype "passive"))
      (node (ref "U600") (pin "15") (pinfunction "BST_15") (pintype "passive"))
    )
    (net (code "29") (name "Net-(U600-CSP)") (class "Default")
      (node (ref "L601") (pin "2") (pinfunction "2_2") (pintype "passive"))
      (node (ref "R605") (pin "1") (pinfunction "1_1") (pintype "passive"))
      (node (ref "U600") (pin "10") (pinfunction "CSP_10") (pintype "passive"))
    )
    (net (code "30") (name "Net-(U600-NTC)") (class "Default")
      (node (ref "R610") (pin "2") (pinfunction "2_2") (pintype "passive"))
      (node (ref "R613") (pin "1") (pinfunction "1_1") (pintype "passive"))
      (node (ref "U600") (pin "13") (pinfunction "NTC_13") (pintype "passive"))
    )
    (net (code "31") (name "Net-(U600-SW)") (class "Default")
      (node (ref "C600") (pin "1") (pinfunction "1_1") (pintype "passive"))
      (node (ref "L601") (pin "1") (pinfunction "1_1") (pintype "passive"))
      (node (ref "U600") (pin "1") (pinfunction "SW_1") (pintype "passive"))
    )
    (net (code "32") (name "Net-(U600-TMR)") (class "Default")
      (node (ref "C612") (pin "1") (pinfunction "1_1") (pintype "passive"))
      (node (ref "U600") (pin "14") (pinfunction "TMR_14") (pintype "passive"))
    )
    (net (code "33") (name "Net-(U601-FB)") (class "Default")
      (node (ref "R607") (pin "1") (pinfunction "1_1") (pintype "passive"))
      (node (ref "R612") (pin "2") (pinfunction "2_2") (pintype "passive"))
      (node (ref "U601") (pin "4") (pinfunction "FB_4") (pintype "passive"))
    )
    (net (code "34") (name "Net-(U601-FREQ)") (class "Default")
      (node (ref "C601") (pin "1") (pinfunction "1_1") (pintype "passive"))
      (node (ref "R606") (pin "1") (pinfunction "1_1") (pintype "passive"))
      (node (ref "U601") (pin "3") (pinfunction "FREQ_3") (pintype "passive"))
    )
    (net (code "35") (name "Net-(U602-LX)") (class "Default")
      (node (ref "L602") (pin "1") (pinfunction "1_1") (pintype "passive"))
      (node (ref "U602") (pin "9") (pinfunction "LX_9") (pintype "passive"))
    )
    (net (code "36") (name "Net-(U602-TSS)") (class "Default")
      (node (ref "C621") (pin "2") (pinfunction "2_2") (pintype "passive"))
      (node (ref "U602") (pin "6") (pinfunction "TSS_6") (pintype "open_collector"))
    )
    (net (code "37") (name "USB_VBUS") (class "Default")
      (node (ref "C608") (pin "2") (pinfunction "2_2") (pintype "passive"))
      (node (ref "C609") (pin "2") (pinfunction "2_2") (pintype "passive"))
      (node (ref "D600") (pin "1") (pinfunction "A_1") (pintype "passive"))
      (node (ref "D601") (pin "1") (pinfunction "A_1") (pintype "passive"))
      (node (ref "D602") (pin "2") (pinfunction "A_2") (pintype "passive"))
      (node (ref "R604") (pin "2") (pinfunction "2_2") (pintype "passive"))
      (node (ref "R608") (pin "1") (pinfunction "1_1") (pintype "passive"))
      (node (ref "U600") (pin "2") (pinfunction "VIN_2") (pintype "passive"))
    )
    (net (code "38") (name "VDD_3V3") (class "Default")
      (node (ref "C615") (pin "2") (pinfunction "2_2") (pintype "passive"))
      (node (ref "C616") (pin "2") (pinfunction "2_2") (pintype "passive"))
      (node (ref "L602") (pin "2") (pinfunction "2_2") (pintype "passive"))
      (node (ref "TP604") (pin "1") (pinfunction "TP_1") (pintype "passive"))
      (node (ref "U602") (pin "7") (pinfunction "VOUT/VFB_7") (pintype "power_in"))
    )
    (net (code "39") (name "VDD_5V") (class "Default")
      (node (ref "C614") (pin "2") (pinfunction "2_2") (pintype "passive"))
      (node (ref "Q600") (pin "2") (pinfunction "S_2") (pintype "passive"))
      (node (ref "Q601") (pin "3") (pinfunction "D_3") (pintype "passive"))
      (node (ref "R614") (pin "2") (pinfunction "2_2") (pintype "passive"))
      (node (ref "R616") (pin "2") (pinfunction "2_2") (pintype "passive"))
      (node (ref "R620") (pin "2") (pinfunction "2_2") (pintype "passive"))
      (node (ref "U602") (pin "1") (pinfunction "PVIN_1") (pintype "power_in"))
      (node (ref "U602") (pin "2") (pinfunction "AVIN_2") (pintype "power_in"))
    )
    (net (code "40") (name "VDD_5VA") (class "Default")
      (node (ref "C618") (pin "2") (pinfunction "2_2") (pintype "passive"))
      (node (ref "C619") (pin "2") (pinfunction "2_2") (pintype "passive"))
      (node (ref "C620") (pin "2") (pinfunction "2_2") (pintype "passive"))
      (node (ref "R615") (pin "2") (pinfunction "2_2") (pintype "passive"))
      (node (ref "TP608") (pin "1") (pinfunction "TP_1") (pintype "passive"))
    )
    (net (code "41") (name "VDD_PIC") (class "Default")
      (node (ref "C602") (pin "1") (pinfunction "1_1") (pintype "passive"))
      (node (ref "C603") (pin "2") (pinfunction "2_2") (pintype "passive"))
      (node (ref "C604") (pin "2") (pinfunction "2_2") (pintype "passive"))
      (node (ref "D604") (pin "1") (pinfunction "K_1") (pintype "passive"))
      (node (ref "Q601") (pin "2") (pinfunction "S_2") (pintype "passive"))
      (node (ref "R607") (pin "2") (pinfunction "2_2") (pintype "passive"))
      (node (ref "R621") (pin "2") (pinfunction "2_2") (pintype "passive"))
      (node (ref "TP601") (pin "1") (pinfunction "TP_1") (pintype "passive"))
      (node (ref "U601") (pin "6") (pinfunction "VDD_6") (pintype "passive"))
      (node (ref "U601") (pin "7") (pinfunction "BOOT_7") (pintype "passive"))
    )
    (net (code "42") (name "V_BATT") (class "Default")
      (node (ref "C610") (pin "2") (pinfunction "2_2") (pintype "passive"))
      (node (ref "C611") (pin "2") (pinfunction "2_2") (pintype "passive"))
      (node (ref "D603") (pin "2") (pinfunction "A_2") (pintype "passive"))
      (node (ref "J600") (pin "1") (pinfunction "1_1") (pintype "passive"))
      (node (ref "R600") (pin "2") (pinfunction "2_2") (pintype "passive"))
      (node (ref "R605") (pin "2") (pinfunction "2_2") (pintype "passive"))
      (node (ref "R624") (pin "2") (pinfunction "2_2") (pintype "passive"))
      (node (ref "U600") (pin "9") (pinfunction "BATT_9") (pintype "passive"))
    )
    (net (code "43") (name "unconnected-(U600-NC-Pad7)") (class "Default")
      (node (ref "U600") (pin "7") (pinfunction "NC_7") (pintype "passive+no_connect"))
    )
  )
)
